# 1_cover.net
KiCad netlist of a schematic drawn in Altium Designer
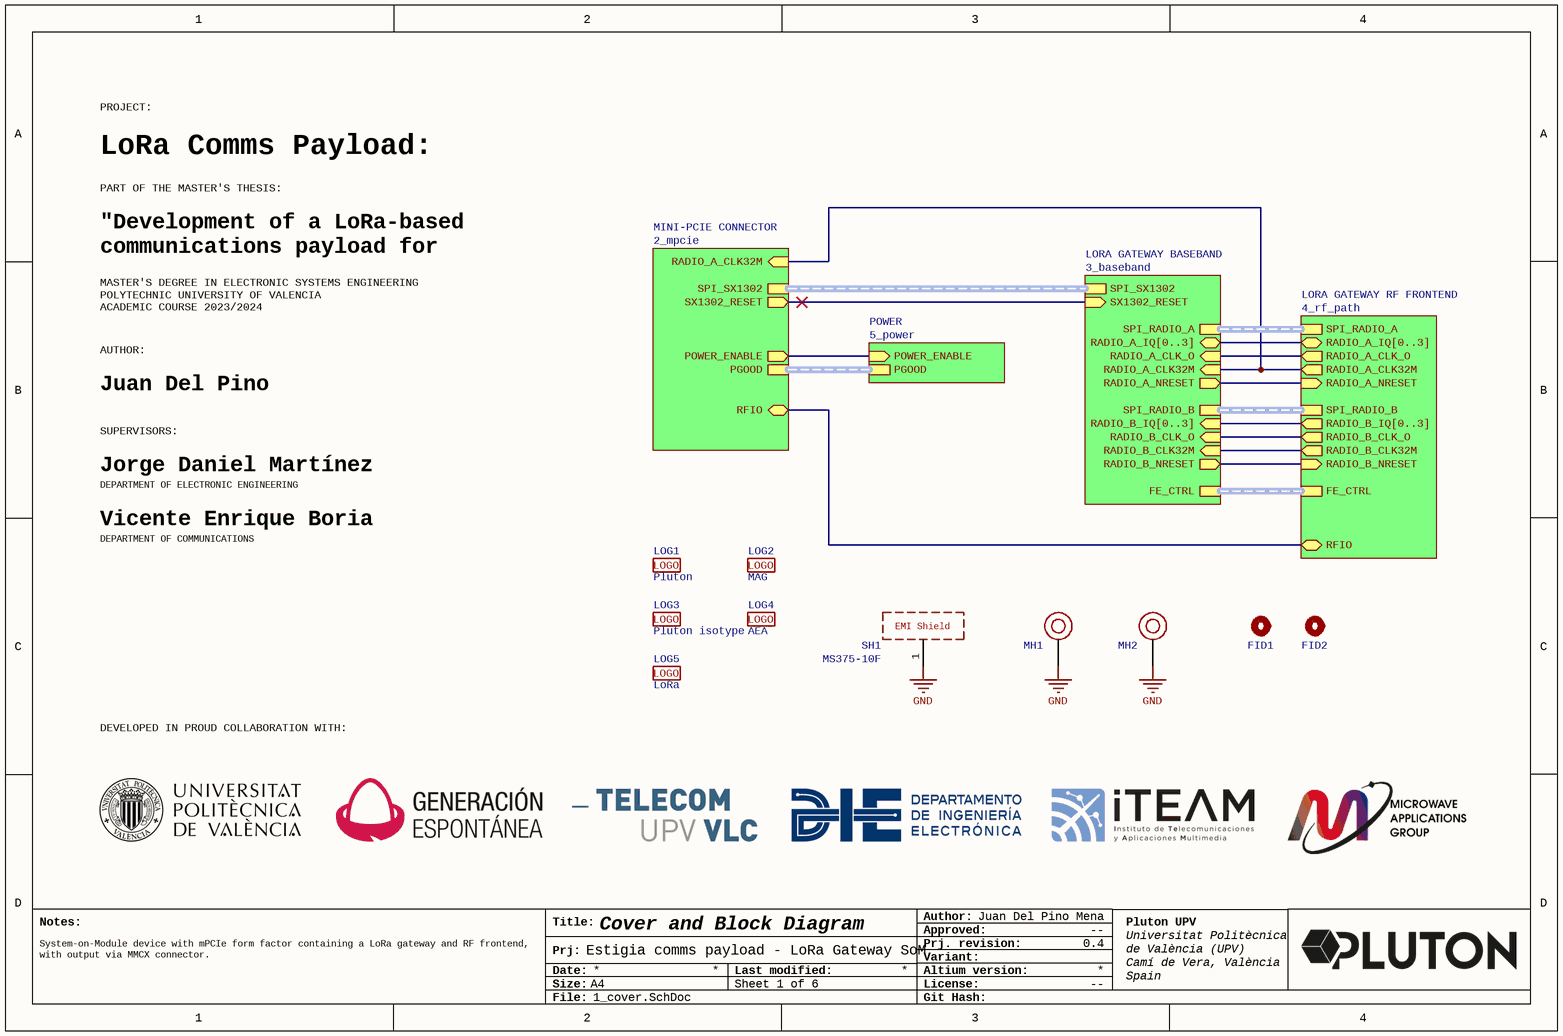
[diagram p0: 1_cover.SchDoc]

(export (version "E")
  (design (tool "Eeschema 10.0.6"))
  (components
    (comp (ref "FID1")
      (value "Fiducial Mark")
      (footprint "Fiducial_1_3_mm")
      (description "FIducial Mark (concentric 1 mm, 3 mm)")
      (libsource (lib "fiducial") (part "Fiducial Mark"))
    )
    (comp (ref "FID2")
      (value "Fiducial Mark")
      (footprint "Fiducial_1_3_mm")
      (description "FIducial Mark (concentric 1 mm, 3 mm)")
      (libsource (lib "fiducial") (part "Fiducial Mark"))
    )
    (comp (ref "LOG1")
      (value "Pluton")
      (footprint "logos:logo_pluton_small")
      (libsource (lib "logos") (part "Logo"))
    )
    (comp (ref "LOG2") (value "MAG") (footprint "logos:logo_mag") (libsource (lib "logos") (part "Logo")))
    (comp (ref "LOG3")
      (value "Pluton isotype")
      (footprint "logos:logo_pluton_isotype_small")
      (libsource (lib "logos") (part "Logo"))
    )
    (comp (ref "LOG4") (value "AEA") (footprint "logos:logo_aea") (libsource (lib "logos") (part "Logo")))
    (comp (ref "LOG5") (value "LoRa") (footprint "logos:logo_lora") (libsource (lib "logos") (part "Logo")))
    (comp (ref "MH1")
      (value "M2.5")
      (footprint "MH mPCIe M2.5")
      (description "Mounting Hole M2.5 for mPCIe")
      (libsource (lib "mounting_holes") (part "MH M2.5 Mounting hole"))
    )
    (comp (ref "MH2")
      (value "M2.5")
      (footprint "MH mPCIe M2.5")
      (description "Mounting Hole M2.5 for mPCIe")
      (libsource (lib "mounting_holes") (part "MH M2.5 Mounting hole"))
    )
    (comp (ref "SH1")
      (value "MS375-10F")
      (footprint "MS375-10F")
      (libsource (lib "shields") (part "Masach shield MS375-10F"))
    )
  )
  (nets
    (net (code "17") (name "GND") (class "Default")
      (node (ref "MH1") (pin "1") (pinfunction "1_1") (pintype "passive"))
      (node (ref "MH2") (pin "1") (pinfunction "1_1") (pintype "passive"))
      (node (ref "SH1") (pin "1") (pinfunction "1_1") (pintype "passive"))
    )
  )
)
